# Buffers.net
KiCad netlist of a schematic drawn in Altium Designer
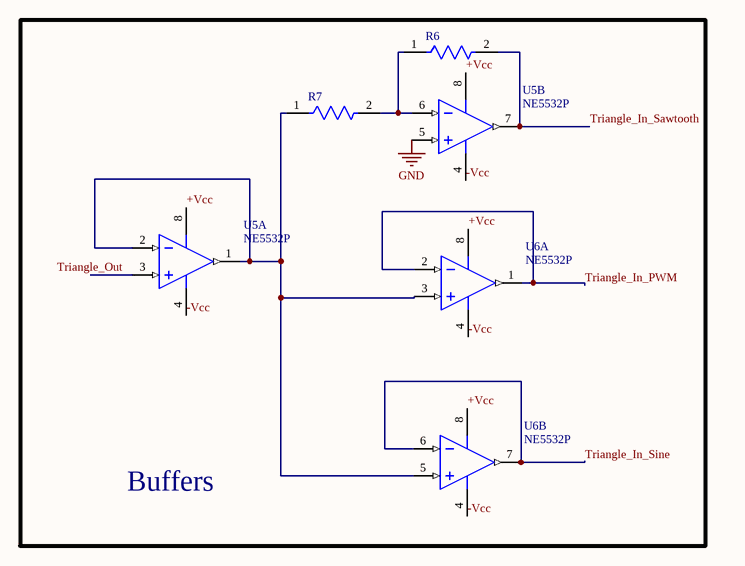
[diagram p0: Buffers.SchDoc]

(export (version "E")
  (design (tool "Eeschema 10.0.6"))
  (components
    (comp (ref "R6")
      (value "~")
      (footprint "FP-VR37-MFG")
      (description "RES 1.2M OHM 5% 1/2W AXIAL")
      (fields (field (name "TOLERANCE") "5%"))
      (libsource (lib "Altium Content Vault") (part "1029c3af85768c4190bb7ad29bc67b5"))
    )
    (comp (ref "R7")
      (value "~")
      (footprint "FP-VR37-MFG")
      (description "RES 1.2M OHM 5% 1/2W AXIAL")
      (fields (field (name "TOLERANCE") "5%"))
      (libsource (lib "Altium Content Vault") (part "1029c3af85768c4190bb7ad29bc67b5"))
    )
    (comp (ref "U5")
      (value "NE5532P")
      (footprint "P0008A")
      (fields (field (name "MANUFACTURER") "Texas Instruments"))
      (libsource (lib "Altium Content Vault") (part "TI-AMP-D6-2-8_D"))
    )
    (comp (ref "U6")
      (value "NE5532P")
      (footprint "P0008A")
      (fields (field (name "MANUFACTURER") "Texas Instruments"))
      (libsource (lib "Altium Content Vault") (part "TI-AMP-D6-2-8_D"))
    )
  )
  (nets
    (net (code "1") (name "/+Vcc") (class "Default")
      (node (ref "U5") (pin "8") (pinfunction "VCC+_8") (pintype "power_in"))
      (node (ref "U6") (pin "8") (pinfunction "VCC+_8") (pintype "power_in"))
    )
    (net (code "2") (name "/-Vcc") (class "Default")
      (node (ref "U5") (pin "4") (pinfunction "VCC-_4") (pintype "power_in"))
      (node (ref "U6") (pin "4") (pinfunction "VCC-_4") (pintype "power_in"))
    )
    (net (code "3") (name "/Triangle_In_PWM") (class "Default")
      (node (ref "U6") (pin "1") (pinfunction "OUT1_1") (pintype "output"))
      (node (ref "U6") (pin "2") (pinfunction "IN1-_2") (pintype "input"))
    )
    (net (code "4") (name "/Triangle_In_Sawtooth") (class "Default")
      (node (ref "R6") (pin "2") (pinfunction "2_2") (pintype "passive"))
      (node (ref "U5") (pin "7") (pinfunction "OUT2_7") (pintype "output"))
    )
    (net (code "5") (name "/Triangle_In_Sine") (class "Default")
      (node (ref "U6") (pin "6") (pinfunction "IN2-_6") (pintype "input"))
      (node (ref "U6") (pin "7") (pinfunction "OUT2_7") (pintype "output"))
    )
    (net (code "6") (name "/Triangle_Out") (class "Default")
      (node (ref "U5") (pin "3") (pinfunction "IN1+_3") (pintype "input"))
    )
    (net (code "7") (name "GND") (class "Default")
      (node (ref "U5") (pin "5") (pinfunction "IN2+_5") (pintype "input"))
    )
    (net (code "8") (name "Net-(U5A-IN1-)") (class "Default")
      (node (ref "R7") (pin "1") (pinfunction "1_1") (pintype "passive"))
      (node (ref "U5") (pin "1") (pinfunction "OUT1_1") (pintype "output"))
      (node (ref "U5") (pin "2") (pinfunction "IN1-_2") (pintype "input"))
      (node (ref "U6") (pin "3") (pinfunction "IN1+_3") (pintype "input"))
      (node (ref "U6") (pin "5") (pinfunction "IN2+_5") (pintype "input"))
    )
    (net (code "9") (name "Net-(U5B-IN2-)") (class "Default")
      (node (ref "R6") (pin "1") (pinfunction "1_1") (pintype "passive"))
      (node (ref "R7") (pin "2") (pinfunction "2_2") (pintype "passive"))
      (node (ref "U5") (pin "6") (pinfunction "IN2-_6") (pintype "input"))
    )
  )
)
